# SCH_d_01_e_02.net
KiCad netlist of a schematic drawn in EasyEDA
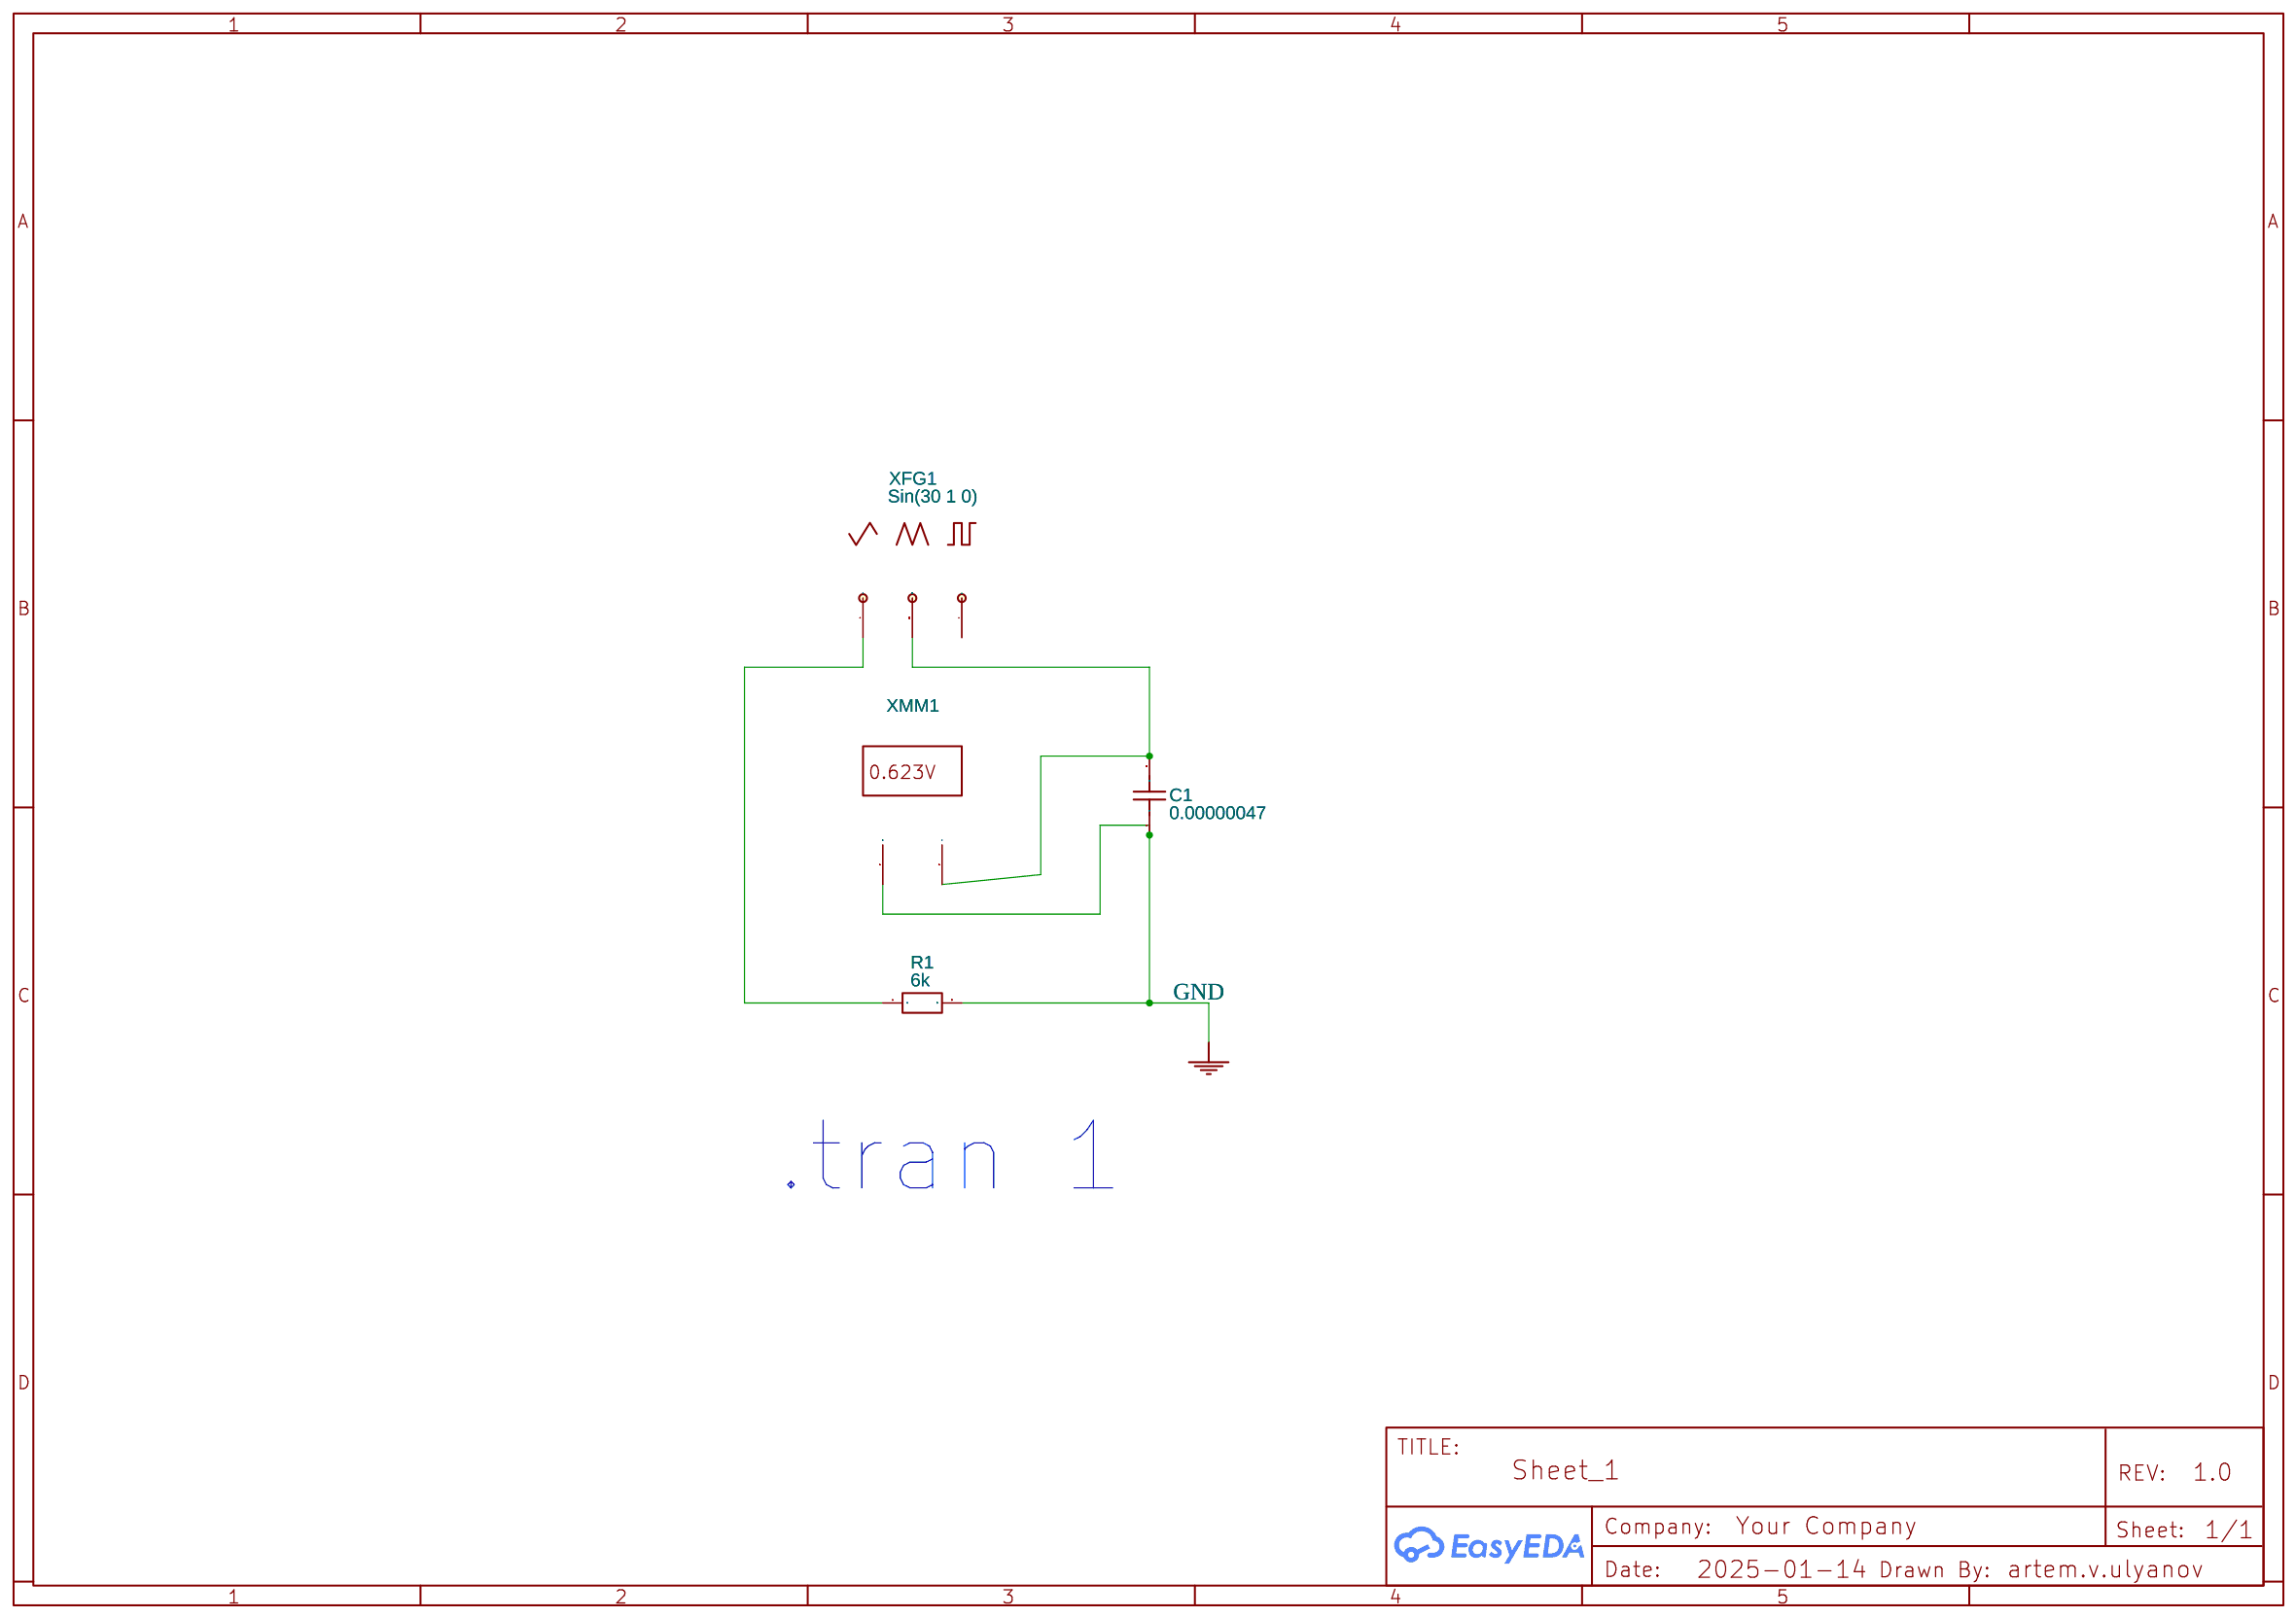
[diagram p0: schematic sheet]

(export (version "E")
  (design (tool "Eeschema 10.0.6"))
  (components
    (comp (ref "C1") (value "0.00000047") (libsource (lib "") (part "Capacitor_US")))
    (comp (ref "R1") (value "6k") (libsource (lib "") (part "R_0603_EU")))
    (comp (ref "XFG1") (value "Sin(30 1 0)") (libsource (lib "") (part "FUNCTIONGENERATOR")))
    (comp (ref "XMM1") (value "Multimeter") (libsource (lib "") (part "MULTIMETER")))
  )
  (nets
    (net (code "1") (name "GND") (class "Default")
      (node (ref "C1") (pin "1") (pinfunction "1_1") (pintype "unspecified"))
      (node (ref "R1") (pin "2") (pinfunction "2_2") (pintype "unspecified"))
      (node (ref "XMM1") (pin "1") (pinfunction "+_1") (pintype "unspecified"))
    )
    (net (code "2") (name "Net-(R1-Pad1)") (class "Default")
      (node (ref "R1") (pin "1") (pinfunction "1_1") (pintype "unspecified"))
      (node (ref "XFG1") (pin "+") (pinfunction "+_+") (pintype "unspecified"))
    )
    (net (code "3") (name "Net-(XMM1-I)") (class "Default")
      (node (ref "C1") (pin "2") (pinfunction "2_2") (pintype "unspecified"))
      (node (ref "XFG1") (pin "COM") (pinfunction "COM_COM") (pintype "unspecified"))
      (node (ref "XMM1") (pin "2") (pinfunction "I_2") (pintype "unspecified"))
    )
    (net (code "4") (name "unconnected-(XFG1-Pad-)") (class "Default")
      (node (ref "XFG1") (pin "-") (pinfunction "-_-") (pintype "unspecified"))
    )
  )
)
